# Schematic_proiect_1_v25.net
KiCad netlist of a schematic drawn in EAGLE
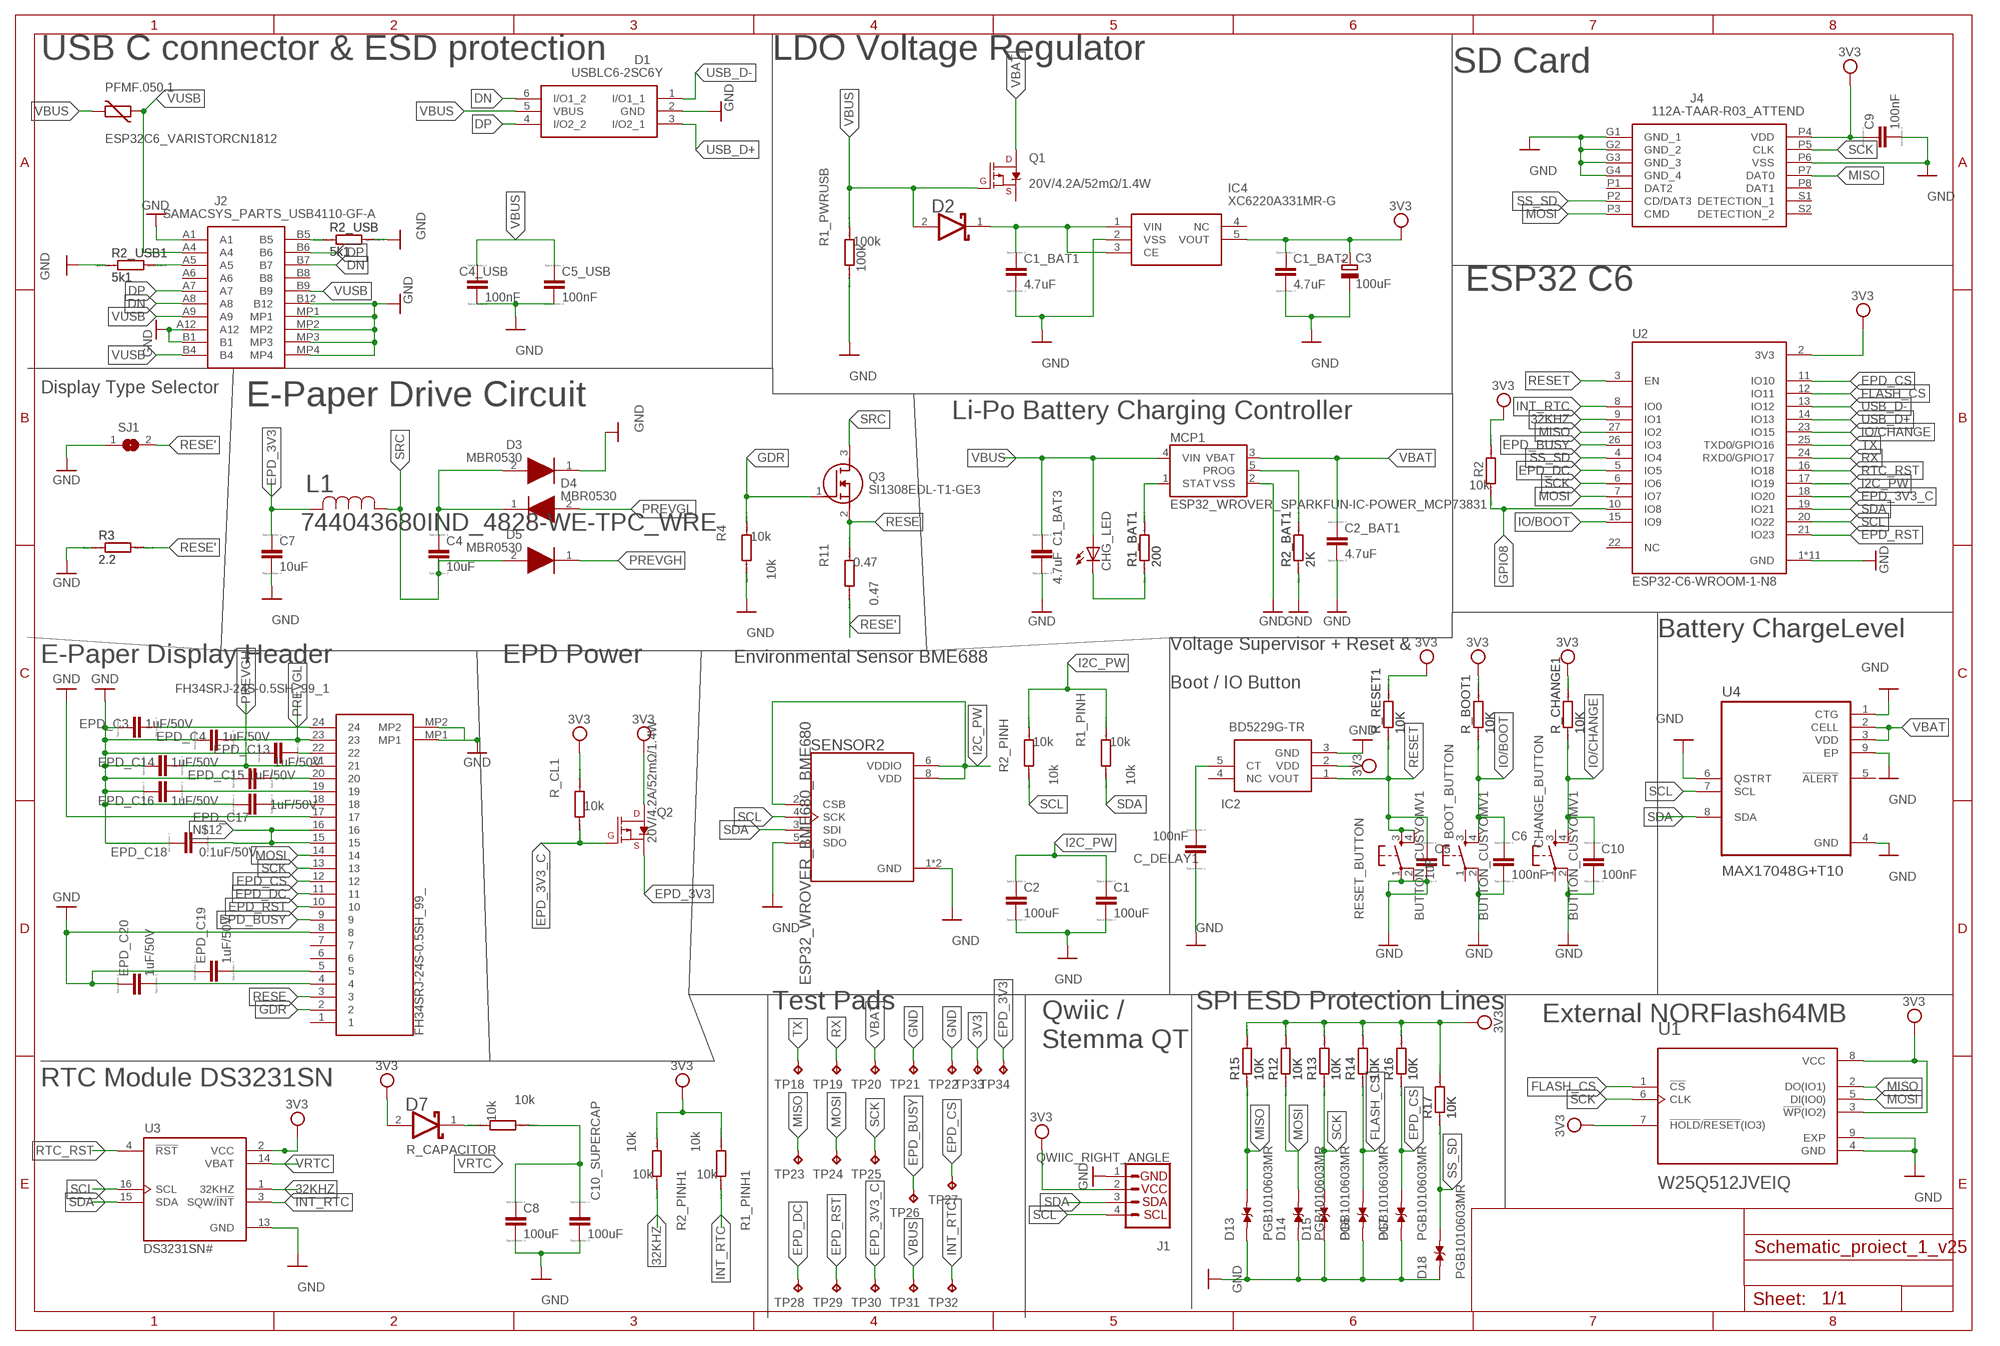
[diagram p0: schematic, sheet 1]

(export (version "E")
  (design (tool "Eeschema 10.0.6"))
  (components
    (comp (ref "BOOT_BUTTON")
      (value "BUTTON_CUSYOMV1")
      (footprint "eagle-import:MYBUTTON")
      (libsource (lib "eagle-import") (part "BUTTON_CUSYOMV1"))
    )
    (comp (ref "C1")
      (value "100uF")
      (footprint "eagle-import:EAGLE-LTSPICE_C0402")
      (libsource (lib "eagle-import") (part "EAGLE-LTSPICE_CC0402"))
    )
    (comp (ref "C1_BAT1")
      (value "4.7uF")
      (footprint "eagle-import:EAGLE-LTSPICE_C0402")
      (libsource (lib "eagle-import") (part "EAGLE-LTSPICE_CC0402"))
    )
    (comp (ref "C1_BAT2")
      (value "4.7uF")
      (footprint "eagle-import:EAGLE-LTSPICE_C0402")
      (libsource (lib "eagle-import") (part "EAGLE-LTSPICE_CC0402"))
    )
    (comp (ref "C1_BAT3")
      (value "4.7uF")
      (footprint "eagle-import:EAGLE-LTSPICE_C0402")
      (libsource (lib "eagle-import") (part "EAGLE-LTSPICE_CC0402"))
    )
    (comp (ref "C2")
      (value "100uF")
      (footprint "eagle-import:EAGLE-LTSPICE_C0402")
      (libsource (lib "eagle-import") (part "EAGLE-LTSPICE_CC0402"))
    )
    (comp (ref "C2_BAT1")
      (value "4.7uF")
      (footprint "eagle-import:EAGLE-LTSPICE_C0402")
      (libsource (lib "eagle-import") (part "EAGLE-LTSPICE_CC0402"))
    )
    (comp (ref "C3")
      (value "100uF")
      (footprint "eagle-import:RCL_CT3528")
      (libsource (lib "eagle-import") (part "RCL_CPOL-EUCT3528"))
    )
    (comp (ref "C4")
      (value "10uF")
      (footprint "eagle-import:EAGLE-LTSPICE_C0402")
      (libsource (lib "eagle-import") (part "EAGLE-LTSPICE_CC0402"))
    )
    (comp (ref "C4_USB")
      (value "100nF")
      (footprint "eagle-import:EAGLE-LTSPICE_C0402")
      (libsource (lib "eagle-import") (part "EAGLE-LTSPICE_CC0402"))
    )
    (comp (ref "C5")
      (value "1uF")
      (footprint "eagle-import:EAGLE-LTSPICE_C0402")
      (libsource (lib "eagle-import") (part "EAGLE-LTSPICE_CC0402"))
    )
    (comp (ref "C5_USB")
      (value "100nF")
      (footprint "eagle-import:EAGLE-LTSPICE_C0402")
      (libsource (lib "eagle-import") (part "EAGLE-LTSPICE_CC0402"))
    )
    (comp (ref "C6")
      (value "100nF")
      (footprint "eagle-import:EAGLE-LTSPICE_C0402")
      (libsource (lib "eagle-import") (part "EAGLE-LTSPICE_CC0402"))
    )
    (comp (ref "C7")
      (value "10uF")
      (footprint "eagle-import:EAGLE-LTSPICE_C0402")
      (libsource (lib "eagle-import") (part "EAGLE-LTSPICE_CC0402"))
    )
    (comp (ref "C8")
      (value "100uF")
      (footprint "eagle-import:EAGLE-LTSPICE_C0402")
      (libsource (lib "eagle-import") (part "EAGLE-LTSPICE_CC0402"))
    )
    (comp (ref "C9")
      (value "100nF")
      (footprint "eagle-import:EAGLE-LTSPICE_C0402")
      (libsource (lib "eagle-import") (part "EAGLE-LTSPICE_CC0402"))
    )
    (comp (ref "C10")
      (value "100nF")
      (footprint "eagle-import:EAGLE-LTSPICE_C0402")
      (libsource (lib "eagle-import") (part "EAGLE-LTSPICE_CC0402"))
    )
    (comp (ref "C10_SUPERCAP")
      (value "100uF")
      (footprint "eagle-import:EAGLE-LTSPICE_C0402")
      (libsource (lib "eagle-import") (part "EAGLE-LTSPICE_CC0402"))
    )
    (comp (ref "CHANGE_BUTTON")
      (value "BUTTON_CUSYOMV1")
      (footprint "eagle-import:MYBUTTON")
      (libsource (lib "eagle-import") (part "BUTTON_CUSYOMV1"))
    )
    (comp (ref "CHG_LED")
      (value "ADAFRUIT_LEDCHIP-LED0603")
      (footprint "eagle-import:ADAFRUIT_CHIP-LED0603")
      (libsource (lib "eagle-import") (part "ADAFRUIT_LEDCHIP-LED0603"))
    )
    (comp (ref "C_DELAY1")
      (value "100nF")
      (footprint "eagle-import:EAGLE-LTSPICE_C0402")
      (libsource (lib "eagle-import") (part "EAGLE-LTSPICE_CC0402"))
    )
    (comp (ref "D1")
      (value "USBLC6-2SC6Y")
      (footprint "eagle-import:SOT95P280X145-6N")
      (fields (field (name "MF") "STMicroelectronics"))
      (libsource (lib "eagle-import") (part "USBLC6-2SC6Y"))
    )
    (comp (ref "D2")
      (value "ESP32_WROVER_AVX---SD0805S020S1R0_AVX_SD0805S020S1R0_0_0AVX_SD0805S020S1R0_0_0")
      (footprint "eagle-import:ESP32_WROVER_AVX---SD0805S020S1R0_AVX_SD0805S020S1R0_0")
      (fields
        (field (name "DIGIKEY_PART_NUMBER") "478-7800-1-ND")
        (field (name "MF") "AVX")
        (field (name "MOUSER_PART_NUMBER") "581-SD0805S020S1R0")
      )
      (libsource (lib "eagle-import") (part "ESP32_WROVER_AVX---SD0805S020S1R0_AVX_SD0805S020S1R0_0_0AVX_SD0805S020S1R0_0_0"))
    )
    (comp (ref "D3")
      (value "MBR0530")
      (footprint "eagle-import:SOD3716X135N")
      (fields (field (name "MF") "ON Semiconductor"))
      (libsource (lib "eagle-import") (part "MBR0530"))
    )
    (comp (ref "D4")
      (value "MBR0530")
      (footprint "eagle-import:SOD3716X135N")
      (fields (field (name "MF") "ON Semiconductor"))
      (libsource (lib "eagle-import") (part "MBR0530"))
    )
    (comp (ref "D5")
      (value "MBR0530")
      (footprint "eagle-import:SOD3716X135N")
      (fields (field (name "MF") "ON Semiconductor"))
      (libsource (lib "eagle-import") (part "MBR0530"))
    )
    (comp (ref "D7")
      (value "ESP32_WROVER_AVX---SD0805S020S1R0_AVX_SD0805S020S1R0_0_0AVX_SD0805S020S1R0_0_0")
      (footprint "eagle-import:ESP32_WROVER_AVX---SD0805S020S1R0_AVX_SD0805S020S1R0_0")
      (fields
        (field (name "DIGIKEY_PART_NUMBER") "478-7800-1-ND")
        (field (name "MF") "AVX")
        (field (name "MOUSER_PART_NUMBER") "581-SD0805S020S1R0")
      )
      (libsource (lib "eagle-import") (part "ESP32_WROVER_AVX---SD0805S020S1R0_AVX_SD0805S020S1R0_0_0AVX_SD0805S020S1R0_0_0"))
    )
    (comp (ref "D13")
      (value "PGB1010603MR")
      (footprint "eagle-import:DIOC1608X36N")
      (fields (field (name "MF") "Littelfuse Inc."))
      (libsource (lib "eagle-import") (part "PGB1010603MR"))
    )
    (comp (ref "D14")
      (value "PGB1010603MR")
      (footprint "eagle-import:DIOC1608X36N")
      (fields (field (name "MF") "Littelfuse Inc."))
      (libsource (lib "eagle-import") (part "PGB1010603MR"))
    )
    (comp (ref "D15")
      (value "PGB1010603MR")
      (footprint "eagle-import:DIOC1608X36N")
      (fields (field (name "MF") "Littelfuse Inc."))
      (libsource (lib "eagle-import") (part "PGB1010603MR"))
    )
    (comp (ref "D16")
      (value "PGB1010603MR")
      (footprint "eagle-import:DIOC1608X36N")
      (fields (field (name "MF") "Littelfuse Inc."))
      (libsource (lib "eagle-import") (part "PGB1010603MR"))
    )
    (comp (ref "D17")
      (value "PGB1010603MR")
      (footprint "eagle-import:DIOC1608X36N")
      (fields (field (name "MF") "Littelfuse Inc."))
      (libsource (lib "eagle-import") (part "PGB1010603MR"))
    )
    (comp (ref "D18")
      (value "PGB1010603MR")
      (footprint "eagle-import:DIOC1608X36N")
      (fields (field (name "MF") "Littelfuse Inc."))
      (libsource (lib "eagle-import") (part "PGB1010603MR"))
    )
    (comp (ref "EPD_C3")
      (value "1uF/50V")
      (footprint "eagle-import:EAGLE-LTSPICE_C0402")
      (libsource (lib "eagle-import") (part "EAGLE-LTSPICE_CC0402"))
    )
    (comp (ref "EPD_C4")
      (value "1uF/50V")
      (footprint "eagle-import:EAGLE-LTSPICE_C0402")
      (libsource (lib "eagle-import") (part "EAGLE-LTSPICE_CC0402"))
    )
    (comp (ref "EPD_C13")
      (value "1uF/50V")
      (footprint "eagle-import:EAGLE-LTSPICE_C0402")
      (libsource (lib "eagle-import") (part "EAGLE-LTSPICE_CC0402"))
    )
    (comp (ref "EPD_C14")
      (value "1uF/50V")
      (footprint "eagle-import:EAGLE-LTSPICE_C0402")
      (libsource (lib "eagle-import") (part "EAGLE-LTSPICE_CC0402"))
    )
    (comp (ref "EPD_C15")
      (value "1uF/50V")
      (footprint "eagle-import:EAGLE-LTSPICE_C0402")
      (libsource (lib "eagle-import") (part "EAGLE-LTSPICE_CC0402"))
    )
    (comp (ref "EPD_C16")
      (value "1uF/50V")
      (footprint "eagle-import:EAGLE-LTSPICE_C0402")
      (libsource (lib "eagle-import") (part "EAGLE-LTSPICE_CC0402"))
    )
    (comp (ref "EPD_C17")
      (value "1uF/50V")
      (footprint "eagle-import:EAGLE-LTSPICE_C0402")
      (libsource (lib "eagle-import") (part "EAGLE-LTSPICE_CC0402"))
    )
    (comp (ref "EPD_C18")
      (value "0.1uF/50V")
      (footprint "eagle-import:EAGLE-LTSPICE_C0402")
      (libsource (lib "eagle-import") (part "EAGLE-LTSPICE_CC0402"))
    )
    (comp (ref "EPD_C19")
      (value "1uF/50V")
      (footprint "eagle-import:EAGLE-LTSPICE_C0402")
      (libsource (lib "eagle-import") (part "EAGLE-LTSPICE_CC0402"))
    )
    (comp (ref "EPD_C20")
      (value "1uF/50V")
      (footprint "eagle-import:EAGLE-LTSPICE_C0402")
      (libsource (lib "eagle-import") (part "EAGLE-LTSPICE_CC0402"))
    )
    (comp (ref "FH34SRJ-24S-0.5SH_99_1")
      (value "FH34SRJ-24S-0.5SH_99_")
      (footprint "eagle-import:FH34SRJ24S05SH99")
      (fields
        (field (name "MANUFACTURER_PART_NUMBER") "FH34SRJ-24S-0.5SH(99)")
        (field (name "MOUSER_PART_NUMBER") "798-FH34SRJ24S05SH99")
      )
      (libsource (lib "eagle-import") (part "FH34SRJ-24S-0.5SH_99_"))
    )
    (comp (ref "IC2")
      (value "BD5229G-TR")
      (footprint "eagle-import:SOT95P280X125-5N")
      (fields (field (name "MOUSER_PART_NUMBER") "755-BD5229G-TR"))
      (libsource (lib "eagle-import") (part "BD5229G-TR"))
    )
    (comp (ref "IC4")
      (value "XC6220A331MR-G")
      (footprint "eagle-import:SOT95P280X120-5N")
      (fields (field (name "MOUSER_PART_NUMBER") "865-XC6220A331MR-G"))
      (libsource (lib "eagle-import") (part "XC6220A331MR-G"))
    )
    (comp (ref "J1")
      (value "QWIIC_RIGHT_ANGLE")
      (footprint "eagle-import:JST04_1MM_RA")
      (libsource (lib "eagle-import") (part "QWIIC_CONNECTORJS-1MM"))
    )
    (comp (ref "J2")
      (value "SAMACSYS_PARTS_USB4110-GF-A")
      (footprint "eagle-import:SAMACSYS_PARTS_USB4110GFA")
      (fields
        (field (name "MANUFACTURER_PART_NUMBER") "USB4110-GF-A")
        (field (name "MOUSER_PART_NUMBER") "640-USB4110-GF-A")
      )
      (libsource (lib "eagle-import") (part "SAMACSYS_PARTS_USB4110-GF-A"))
    )
    (comp (ref "J4")
      (value "112A-TAAR-R03_ATTEND")
      (footprint "eagle-import:112ATAARR03ATTEND")
      (fields (field (name "MANUFACTURER_PART_NUMBER") "112A-TAAR-R03 ATTEND"))
      (libsource (lib "eagle-import") (part "112A-TAAR-R03_ATTEND"))
    )
    (comp (ref "L1")
      (value "744043680IND_4828-WE-TPC_WRE")
      (footprint "eagle-import:IND_4828-WE-TPC_WRE")
      (fields
        (field (name "MANUFACTURER_PART_NUMBER") "744043680")
        (field (name "COPYRIGHT") "Copyright (C) 2024 Ultra Librarian. All rights reserved.")
      )
      (libsource (lib "eagle-import") (part "744043680IND_4828-WE-TPC_WRE"))
    )
    (comp (ref "MCP1")
      (value "ESP32_WROVER_SPARKFUN-IC-POWER_MCP73831")
      (footprint "eagle-import:ESP32_WROVER_SPARKFUN-IC-POWER_SOT23-5")
      (libsource (lib "eagle-import") (part "ESP32_WROVER_SPARKFUN-IC-POWER_MCP73831"))
    )
    (comp (ref "PFMF.050.1")
      (value "ESP32C6_VARISTORCN1812")
      (footprint "eagle-import:ESP32C6_VARISTOR_CT_CN1812")
      (libsource (lib "eagle-import") (part "ESP32C6_VARISTORCN1812"))
    )
    (comp (ref "Q1")
      (value "20V/4.2A/52mΩ/1.4W")
      (footprint "eagle-import:ESP32_WROVER_SPARKFUN-DISCRETESEMI_SOT23-3")
      (libsource (lib "eagle-import") (part "ESP32_WROVER_SPARKFUN-DISCRETESEMI_MOSFET_PCH-DMG2305UX-7"))
    )
    (comp (ref "Q2")
      (value "20V/4.2A/52mΩ/1.4W")
      (footprint "eagle-import:ESP32_WROVER_SPARKFUN-DISCRETESEMI_SOT23-3")
      (libsource (lib "eagle-import") (part "ESP32_WROVER_SPARKFUN-DISCRETESEMI_MOSFET_PCH-DMG2305UX-7"))
    )
    (comp (ref "Q3")
      (value "SI1308EDL-T1-GE3")
      (footprint "eagle-import:SOT65P210X110-3N")
      (fields (field (name "MF") "Vishay Siliconix"))
      (libsource (lib "eagle-import") (part "SI1308EDL-T1-GE3"))
    )
    (comp (ref "R1_BAT1")
      (value "200")
      (footprint "eagle-import:ESP32_WROVER_EAGLE-LTSPICE_R0402")
      (libsource (lib "eagle-import") (part "ESP32_WROVER_EAGLE-LTSPICE_RR0402"))
    )
    (comp (ref "R1_PINH")
      (value "10k")
      (footprint "eagle-import:ESP32_WROVER_EAGLE-LTSPICE_R0402")
      (libsource (lib "eagle-import") (part "ESP32_WROVER_EAGLE-LTSPICE_RR0402"))
    )
    (comp (ref "R1_PINH1")
      (value "10k")
      (footprint "eagle-import:ESP32_WROVER_EAGLE-LTSPICE_R0402")
      (libsource (lib "eagle-import") (part "ESP32_WROVER_EAGLE-LTSPICE_RR0402"))
    )
    (comp (ref "R1_PWRUSB")
      (value "100k")
      (footprint "eagle-import:ESP32_WROVER_EAGLE-LTSPICE_R0402")
      (libsource (lib "eagle-import") (part "ESP32_WROVER_EAGLE-LTSPICE_RR0402"))
    )
    (comp (ref "R2")
      (value "10k")
      (footprint "eagle-import:ESP32_WROVER_EAGLE-LTSPICE_R0402")
      (libsource (lib "eagle-import") (part "ESP32_WROVER_EAGLE-LTSPICE_RR0402"))
    )
    (comp (ref "R2_BAT1")
      (value "2K")
      (footprint "eagle-import:ESP32_WROVER_EAGLE-LTSPICE_R0402")
      (libsource (lib "eagle-import") (part "ESP32_WROVER_EAGLE-LTSPICE_RR0402"))
    )
    (comp (ref "R2_PINH")
      (value "10k")
      (footprint "eagle-import:ESP32_WROVER_EAGLE-LTSPICE_R0402")
      (libsource (lib "eagle-import") (part "ESP32_WROVER_EAGLE-LTSPICE_RR0402"))
    )
    (comp (ref "R2_PINH1")
      (value "10k")
      (footprint "eagle-import:ESP32_WROVER_EAGLE-LTSPICE_R0402")
      (libsource (lib "eagle-import") (part "ESP32_WROVER_EAGLE-LTSPICE_RR0402"))
    )
    (comp (ref "R2_USB")
      (value "5k1")
      (footprint "eagle-import:ESP32_WROVER_EAGLE-LTSPICE_R0402")
      (libsource (lib "eagle-import") (part "ESP32_WROVER_EAGLE-LTSPICE_RR0402"))
    )
    (comp (ref "R2_USB1")
      (value "5k1")
      (footprint "eagle-import:ESP32_WROVER_EAGLE-LTSPICE_R0402")
      (libsource (lib "eagle-import") (part "ESP32_WROVER_EAGLE-LTSPICE_RR0402"))
    )
    (comp (ref "R3")
      (value "2.2")
      (footprint "eagle-import:ESP32_WROVER_EAGLE-LTSPICE_R0402")
      (libsource (lib "eagle-import") (part "ESP32_WROVER_EAGLE-LTSPICE_RR0402"))
    )
    (comp (ref "R4")
      (value "10k")
      (footprint "eagle-import:ESP32_WROVER_EAGLE-LTSPICE_R0402")
      (libsource (lib "eagle-import") (part "ESP32_WROVER_EAGLE-LTSPICE_RR0402"))
    )
    (comp (ref "R11")
      (value "0.47")
      (footprint "eagle-import:ESP32_WROVER_EAGLE-LTSPICE_R0402")
      (libsource (lib "eagle-import") (part "ESP32_WROVER_EAGLE-LTSPICE_RR0402"))
    )
    (comp (ref "R12")
      (value "10K")
      (footprint "eagle-import:ESP32_WROVER_EAGLE-LTSPICE_R0402")
      (libsource (lib "eagle-import") (part "ESP32_WROVER_EAGLE-LTSPICE_RR0402"))
    )
    (comp (ref "R13")
      (value "10K")
      (footprint "eagle-import:ESP32_WROVER_EAGLE-LTSPICE_R0402")
      (libsource (lib "eagle-import") (part "ESP32_WROVER_EAGLE-LTSPICE_RR0402"))
    )
    (comp (ref "R14")
      (value "10K")
      (footprint "eagle-import:ESP32_WROVER_EAGLE-LTSPICE_R0402")
      (libsource (lib "eagle-import") (part "ESP32_WROVER_EAGLE-LTSPICE_RR0402"))
    )
    (comp (ref "R15")
      (value "10K")
      (footprint "eagle-import:ESP32_WROVER_EAGLE-LTSPICE_R0402")
      (libsource (lib "eagle-import") (part "ESP32_WROVER_EAGLE-LTSPICE_RR0402"))
    )
    (comp (ref "R16")
      (value "10K")
      (footprint "eagle-import:ESP32_WROVER_EAGLE-LTSPICE_R0402")
      (libsource (lib "eagle-import") (part "ESP32_WROVER_EAGLE-LTSPICE_RR0402"))
    )
    (comp (ref "R17")
      (value "10K")
      (footprint "eagle-import:ESP32_WROVER_EAGLE-LTSPICE_R0402")
      (libsource (lib "eagle-import") (part "ESP32_WROVER_EAGLE-LTSPICE_RR0402"))
    )
    (comp (ref "RESET_BUTTON")
      (value "BUTTON_CUSYOMV1")
      (footprint "eagle-import:MYBUTTON")
      (libsource (lib "eagle-import") (part "BUTTON_CUSYOMV1"))
    )
    (comp (ref "R_BOOT1")
      (value "10K")
      (footprint "eagle-import:ESP32_WROVER_EAGLE-LTSPICE_R0402")
      (libsource (lib "eagle-import") (part "ESP32_WROVER_EAGLE-LTSPICE_RR0402"))
    )
    (comp (ref "R_CAPACITOR")
      (value "10k")
      (footprint "eagle-import:ESP32_WROVER_EAGLE-LTSPICE_R0402")
      (libsource (lib "eagle-import") (part "ESP32_WROVER_EAGLE-LTSPICE_RR0402"))
    )
    (comp (ref "R_CHANGE1")
      (value "10K")
      (footprint "eagle-import:ESP32_WROVER_EAGLE-LTSPICE_R0402")
      (libsource (lib "eagle-import") (part "ESP32_WROVER_EAGLE-LTSPICE_RR0402"))
    )
    (comp (ref "R_CL1")
      (value "10k")
      (footprint "eagle-import:ESP32_WROVER_EAGLE-LTSPICE_R0402")
      (libsource (lib "eagle-import") (part "ESP32_WROVER_EAGLE-LTSPICE_RR0402"))
    )
    (comp (ref "R_RESET1")
      (value "10K")
      (footprint "eagle-import:ESP32_WROVER_EAGLE-LTSPICE_R0402")
      (libsource (lib "eagle-import") (part "ESP32_WROVER_EAGLE-LTSPICE_RR0402"))
    )
    (comp (ref "SENSOR2")
      (value "ESP32_WROVER_BME680_BME680")
      (footprint "eagle-import:ESP32_WROVER_BME680_PSON80P300X300X100-8N")
      (fields (field (name "MF") "Bosch Sensortec") (field (name "MP") "BME680"))
      (libsource (lib "eagle-import") (part "ESP32_WROVER_BME680_BME680"))
    )
    (comp (ref "SJ1") (value "SJ") (footprint "eagle-import:SJ") (libsource (lib "eagle-import") (part "SJ")))
    (comp (ref "TP18")
      (value "TPTP20R")
      (footprint "eagle-import:TP20R")
      (libsource (lib "eagle-import") (part "TPTP20R"))
    )
    (comp (ref "TP19")
      (value "TPTP20R")
      (footprint "eagle-import:TP20R")
      (libsource (lib "eagle-import") (part "TPTP20R"))
    )
    (comp (ref "TP20")
      (value "TPTP20R")
      (footprint "eagle-import:TP20R")
      (libsource (lib "eagle-import") (part "TPTP20R"))
    )
    (comp (ref "TP21")
      (value "TPTP20R")
      (footprint "eagle-import:TP20R")
      (libsource (lib "eagle-import") (part "TPTP20R"))
    )
    (comp (ref "TP22")
      (value "TPTP20R")
      (footprint "eagle-import:TP20R")
      (libsource (lib "eagle-import") (part "TPTP20R"))
    )
    (comp (ref "TP23")
      (value "TPTP20R")
      (footprint "eagle-import:TP20R")
      (libsource (lib "eagle-import") (part "TPTP20R"))
    )
    (comp (ref "TP24")
      (value "TPTP20R")
      (footprint "eagle-import:TP20R")
      (libsource (lib "eagle-import") (part "TPTP20R"))
    )
    (comp (ref "TP25")
      (value "TPTP20R")
      (footprint "eagle-import:TP20R")
      (libsource (lib "eagle-import") (part "TPTP20R"))
    )
    (comp (ref "TP26")
      (value "TPTP20R")
      (footprint "eagle-import:TP20R")
      (libsource (lib "eagle-import") (part "TPTP20R"))
    )
    (comp (ref "TP27")
      (value "TPTP20R")
      (footprint "eagle-import:TP20R")
      (libsource (lib "eagle-import") (part "TPTP20R"))
    )
    (comp (ref "TP28")
      (value "TPTP20R")
      (footprint "eagle-import:TP20R")
      (libsource (lib "eagle-import") (part "TPTP20R"))
    )
    (comp (ref "TP29")
      (value "TPTP20R")
      (footprint "eagle-import:TP20R")
      (libsource (lib "eagle-import") (part "TPTP20R"))
    )
    (comp (ref "TP30")
      (value "TPTP20R")
      (footprint "eagle-import:TP20R")
      (libsource (lib "eagle-import") (part "TPTP20R"))
    )
    (comp (ref "TP31")
      (value "TPTP20R")
      (footprint "eagle-import:TP20R")
      (libsource (lib "eagle-import") (part "TPTP20R"))
    )
    (comp (ref "TP32")
      (value "TPTP20R")
      (footprint "eagle-import:TP20R")
      (libsource (lib "eagle-import") (part "TPTP20R"))
    )
    (comp (ref "TP33")
      (value "TPTP20R")
      (footprint "eagle-import:TP20R")
      (libsource (lib "eagle-import") (part "TPTP20R"))
    )
    (comp (ref "TP34")
      (value "TPTP20R")
      (footprint "eagle-import:TP20R")
      (libsource (lib "eagle-import") (part "TPTP20R"))
    )
    (comp (ref "U1")
      (value "W25Q512JVEIQ")
      (footprint "eagle-import:SON127P600X800X80-9N")
      (fields (field (name "MF") "Winbond Electronics"))
      (libsource (lib "eagle-import") (part "W25Q512JVEIQ"))
    )
    (comp (ref "U2")
      (value "ESP32-C6-WROOM-1-N8")
      (footprint "eagle-import:XCVR_ESP32-C6-WROOM-1-N8")
      (fields (field (name "MF") "Espressif Systems"))
      (libsource (lib "eagle-import") (part "ESP32-C6-WROOM-1-N8"))
    )
    (comp (ref "U3")
      (value "DS3231SN#")
      (footprint "eagle-import:SOIC127P1032X265-16N")
      (fields (field (name "MF") "Analog Devices"))
      (libsource (lib "eagle-import") (part "DS3231SN#"))
    )
    (comp (ref "U4")
      (value "MAX17048G+T10")
      (footprint "eagle-import:SON50P200X200X80-9N")
      (fields (field (name "MF") "Analog Devices"))
      (libsource (lib "eagle-import") (part "MAX17048G+T10"))
    )
  )
  (nets
    (net (code "1") (name "3V3") (class "Default")
      (node (ref "C1_BAT2") (pin "1") (pinfunction "1_1") (pintype "passive"))
      (node (ref "C3") (pin "+") (pinfunction "+_+") (pintype "passive"))
      (node (ref "C9") (pin "1") (pinfunction "1_1") (pintype "passive"))
      (node (ref "D7") (pin "2") (pinfunction "ANODE_2") (pintype "bidirectional"))
      (node (ref "IC2") (pin "2") (pinfunction "VDD_2") (pintype "bidirectional"))
      (node (ref "IC4") (pin "5") (pinfunction "VOUT_5") (pintype "bidirectional"))
      (node (ref "J1") (pin "2") (pinfunction "2_2") (pintype "power_in"))
      (node (ref "J4") (pin "P4") (pinfunction "VDD_P4") (pintype "bidirectional"))
      (node (ref "Q2") (pin "3") (pinfunction "D_3") (pintype "bidirectional"))
      (node (ref "R12") (pin "2") (pinfunction "2_2") (pintype "passive"))
      (node (ref "R13") (pin "2") (pinfunction "2_2") (pintype "passive"))
      (node (ref "R14") (pin "2") (pinfunction "2_2") (pintype "passive"))
      (node (ref "R15") (pin "2") (pinfunction "2_2") (pintype "passive"))
      (node (ref "R16") (pin "2") (pinfunction "2_2") (pintype "passive"))
      (node (ref "R17") (pin "2") (pinfunction "2_2") (pintype "passive"))
      (node (ref "R1_PINH1") (pin "1") (pinfunction "1_1") (pintype "passive"))
      (node (ref "R2") (pin "2") (pinfunction "2_2") (pintype "passive"))
      (node (ref "R2_PINH1") (pin "1") (pinfunction "1_1") (pintype "passive"))
      (node (ref "R_BOOT1") (pin "2") (pinfunction "2_2") (pintype "passive"))
      (node (ref "R_CHANGE1") (pin "2") (pinfunction "2_2") (pintype "passive"))
      (node (ref "R_CL1") (pin "2") (pinfunction "2_2") (pintype "passive"))
      (node (ref "R_RESET1") (pin "2") (pinfunction "2_2") (pintype "passive"))
      (node (ref "TP33") (pin "TP") (pinfunction "TP_TP") (pintype "input"))
      (node (ref "U1") (pin "3") (pinfunction "~{WP}(IO2)_3") (pintype "bidirectional"))
      (node (ref "U1") (pin "7") (pinfunction "~{HOLD}/~{RESET}(IO3)_7") (pintype "bidirectional"))
      (node (ref "U1") (pin "8") (pinfunction "VCC_8") (pintype "power_in"))
      (node (ref "U2") (pin "2") (pinfunction "3V3_2") (pintype "power_in"))
      (node (ref "U3") (pin "2") (pinfunction "VCC_2") (pintype "power_in"))
    )
    (net (code "2") (name "32KHZ") (class "Default")
      (node (ref "R2_PINH1") (pin "2") (pinfunction "2_2") (pintype "passive"))
      (node (ref "U2") (pin "9") (pinfunction "IO1_9") (pintype "bidirectional"))
      (node (ref "U3") (pin "1") (pinfunction "32KHZ_1") (pintype "output"))
    )
    (net (code "3") (name "DN") (class "Default")
      (node (ref "D1") (pin "6") (pinfunction "I/O1_2_6") (pintype "bidirectional"))
      (node (ref "J2") (pin "A8") (pinfunction "A8_A8") (pintype "bidirectional"))
      (node (ref "J2") (pin "B7") (pinfunction "B7_B7") (pintype "bidirectional"))
    )
    (net (code "4") (name "DP") (class "Default")
      (node (ref "D1") (pin "4") (pinfunction "I/O2_2_4") (pintype "bidirectional"))
      (node (ref "J2") (pin "A7") (pinfunction "A7_A7") (pintype "bidirectional"))
      (node (ref "J2") (pin "B6") (pinfunction "B6_B6") (pintype "bidirectional"))
    )
    (net (code "5") (name "EPD_3V3") (class "Default")
      (node (ref "C7") (pin "1") (pinfunction "1_1") (pintype "passive"))
      (node (ref "L1") (pin "2") (pinfunction "2_2") (pintype "passive"))
      (node (ref "Q2") (pin "2") (pinfunction "S_2") (pintype "bidirectional"))
      (node (ref "TP34") (pin "TP") (pinfunction "TP_TP") (pintype "input"))
    )
    (net (code "6") (name "EPD_3V3_C") (class "Default")
      (node (ref "Q2") (pin "1") (pinfunction "G_1") (pintype "bidirectional"))
      (node (ref "R_CL1") (pin "1") (pinfunction "1_1") (pintype "passive"))
      (node (ref "TP30") (pin "TP") (pinfunction "TP_TP") (pintype "input"))
      (node (ref "U2") (pin "18") (pinfunction "IO20_18") (pintype "bidirectional"))
    )
    (net (code "7") (name "EPD_BUSY") (class "Default")
      (node (ref "FH34SRJ-24S-0.5SH_99_1") (pin "9") (pinfunction "9_9") (pintype "bidirectional"))
      (node (ref "TP26") (pin "TP") (pinfunction "TP_TP") (pintype "input"))
      (node (ref "U2") (pin "26") (pinfunction "IO3_26") (pintype "bidirectional"))
    )
    (net (code "8") (name "EPD_CS") (class "Default")
      (node (ref "D17") (pin "2") (pinfunction "2_2") (pintype "passive"))
      (node (ref "FH34SRJ-24S-0.5SH_99_1") (pin "12") (pinfunction "12_12") (pintype "bidirectional"))
      (node (ref "R16") (pin "1") (pinfunction "1_1") (pintype "passive"))
      (node (ref "TP27") (pin "TP") (pinfunction "TP_TP") (pintype "input"))
      (node (ref "U2") (pin "11") (pinfunction "IO10_11") (pintype "bidirectional"))
    )
    (net (code "9") (name "EPD_DC") (class "Default")
      (node (ref "FH34SRJ-24S-0.5SH_99_1") (pin "11") (pinfunction "11_11") (pintype "bidirectional"))
      (node (ref "TP28") (pin "TP") (pinfunction "TP_TP") (pintype "input"))
      (node (ref "U2") (pin "5") (pinfunction "IO5_5") (pintype "bidirectional"))
    )
    (net (code "10") (name "EPD_RST") (class "Default")
      (node (ref "FH34SRJ-24S-0.5SH_99_1") (pin "10") (pinfunction "10_10") (pintype "bidirectional"))
      (node (ref "TP29") (pin "TP") (pinfunction "TP_TP") (pintype "input"))
      (node (ref "U2") (pin "21") (pinfunction "IO23_21") (pintype "bidirectional"))
    )
    (net (code "11") (name "FLASH_CS") (class "Default")
      (node (ref "D16") (pin "2") (pinfunction "2_2") (pintype "passive"))
      (node (ref "R14") (pin "1") (pinfunction "1_1") (pintype "passive"))
      (node (ref "U1") (pin "1") (pinfunction "~{CS}_1") (pintype "input"))
      (node (ref "U2") (pin "12") (pinfunction "IO11_12") (pintype "bidirectional"))
    )
    (net (code "12") (name "GDR") (class "Default")
      (node (ref "FH34SRJ-24S-0.5SH_99_1") (pin "2") (pinfunction "2_2") (pintype "bidirectional"))
      (node (ref "Q3") (pin "1") (pinfunction "G_1") (pintype "bidirectional"))
      (node (ref "R4") (pin "2") (pinfunction "2_2") (pintype "passive"))
    )
    (net (code "13") (name "GND") (class "Default")
      (node (ref "BOOT_BUTTON") (pin "2") (pinfunction "2_2") (pintype "passive"))
      (node (ref "C1") (pin "2") (pinfunction "2_2") (pintype "passive"))
      (node (ref "C10") (pin "2") (pinfunction "2_2") (pintype "passive"))
      (node (ref "C10_SUPERCAP") (pin "2") (pinfunction "2_2") (pintype "passive"))
      (node (ref "C1_BAT1") (pin "2") (pinfunction "2_2") (pintype "passive"))
      (node (ref "C1_BAT2") (pin "2") (pinfunction "2_2") (pintype "passive"))
      (node (ref "C1_BAT3") (pin "2") (pinfunction "2_2") (pintype "passive"))
      (node (ref "C2") (pin "2") (pinfunction "2_2") (pintype "passive"))
      (node (ref "C2_BAT1") (pin "2") (pinfunction "2_2") (pintype "passive"))
      (node (ref "C3") (pin "-") (pinfunction "-_-") (pintype "passive"))
      (node (ref "C4_USB") (pin "2") (pinfunction "2_2") (pintype "passive"))
      (node (ref "C5") (pin "2") (pinfunction "2_2") (pintype "passive"))
      (node (ref "C5_USB") (pin "2") (pinfunction "2_2") (pintype "passive"))
      (node (ref "C6") (pin "2") (pinfunction "2_2") (pintype "passive"))
      (node (ref "C7") (pin "2") (pinfunction "2_2") (pintype "passive"))
      (node (ref "C8") (pin "2") (pinfunction "2_2") (pintype "passive"))
      (node (ref "C9") (pin "2") (pinfunction "2_2") (pintype "passive"))
      (node (ref "CHANGE_BUTTON") (pin "2") (pinfunction "2_2") (pintype "passive"))
      (node (ref "C_DELAY1") (pin "1") (pinfunction "1_1") (pintype "passive"))
      (node (ref "D1") (pin "2") (pinfunction "GND_2") (pintype "bidirectional"))
      (node (ref "D13") (pin "1") (pinfunction "1_1") (pintype "passive"))
      (node (ref "D14") (pin "1") (pinfunction "1_1") (pintype "passive"))
      (node (ref "D15") (pin "1") (pinfunction "1_1") (pintype "passive"))
      (node (ref "D16") (pin "1") (pinfunction "1_1") (pintype "passive"))
      (node (ref "D17") (pin "1") (pinfunction "1_1") (pintype "passive"))
      (node (ref "D18") (pin "1") (pinfunction "1_1") (pintype "passive"))
      (node (ref "D3") (pin "1") (pinfunction "K_1") (pintype "bidirectional"))
      (node (ref "EPD_C13") (pin "1") (pinfunction "1_1") (pintype "passive"))
      (node (ref "EPD_C14") (pin "1") (pinfunction "1_1") (pintype "passive"))
      (node (ref "EPD_C15") (pin "1") (pinfunction "1_1") (pintype "passive"))
      (node (ref "EPD_C16") (pin "1") (pinfunction "1_1") (pintype "passive"))
      (node (ref "EPD_C17") (pin "1") (pinfunction "1_1") (pintype "passive"))
      (node (ref "EPD_C18") (pin "1") (pinfunction "1_1") (pintype "passive"))
      (node (ref "EPD_C19") (pin "1") (pinfunction "1_1") (pintype "passive"))
      (node (ref "EPD_C20") (pin "1") (pinfunction "1_1") (pintype "passive"))
      (node (ref "EPD_C3") (pin "1") (pinfunction "1_1") (pintype "passive"))
      (node (ref "EPD_C4") (pin "1") (pinfunction "1_1") (pintype "passive"))
      (node (ref "FH34SRJ-24S-0.5SH_99_1") (pin "17") (pinfunction "17_17") (pintype "bidirectional"))
      (node (ref "FH34SRJ-24S-0.5SH_99_1") (pin "8") (pinfunction "8_8") (pintype "bidirectional"))
      (node (ref "FH34SRJ-24S-0.5SH_99_1") (pin "MP1") (pinfunction "MP1_MP1") (pintype "bidirectional"))
      (node (ref "FH34SRJ-24S-0.5SH_99_1") (pin "MP2") (pinfunction "MP2_MP2") (pintype "bidirectional"))
      (node (ref "IC2") (pin "3") (pinfunction "GND_3") (pintype "bidirectional"))
      (node (ref "IC4") (pin "2") (pinfunction "VSS_2") (pintype "bidirectional"))
      (node (ref "J1") (pin "1") (pinfunction "1_1") (pintype "power_in"))
      (node (ref "J2") (pin "A1") (pinfunction "A1_A1") (pintype "bidirectional"))
      (node (ref "J2") (pin "A12") (pinfunction "A12_A12") (pintype "bidirectional"))
      (node (ref "J2") (pin "B1") (pinfunction "B1_B1") (pintype "bidirectional"))
      (node (ref "J2") (pin "B12") (pinfunction "B12_B12") (pintype "bidirectional"))
      (node (ref "J2") (pin "MP1") (pinfunction "MP1_MP1") (pintype "bidirectional"))
      (node (ref "J2") (pin "MP2") (pinfunction "MP2_MP2") (pintype "bidirectional"))
      (node (ref "J2") (pin "MP3") (pinfunction "MP3_MP3") (pintype "bidirectional"))
      (node (ref "J2") (pin "MP4") (pinfunction "MP4_MP4") (pintype "bidirectional"))
      (node (ref "J4") (pin "G1") (pinfunction "GND_1_G1") (pintype "bidirectional"))
      (node (ref "J4") (pin "G2") (pinfunction "GND_2_G2") (pintype "bidirectional"))
      (node (ref "J4") (pin "G3") (pinfunction "GND_3_G3") (pintype "bidirectional"))
      (node (ref "J4") (pin "G4") (pinfunction "GND_4_G4") (pintype "bidirectional"))
      (node (ref "J4") (pin "P6") (pinfunction "VSS_P6") (pintype "bidirectional"))
      (node (ref "MCP1") (pin "2") (pinfunction "VSS_2") (pintype "power_in"))
      (node (ref "R1_PWRUSB") (pin "1") (pinfunction "1_1") (pintype "passive"))
      (node (ref "R2_BAT1") (pin "1") (pinfunction "1_1") (pintype "passive"))
      (node (ref "R2_USB") (pin "2") (pinfunction "2_2") (pintype "passive"))
      (node (ref "R2_USB1") (pin "1") (pinfunction "1_1") (pintype "passive"))
      (node (ref "R3") (pin "1") (pinfunction "1_1") (pintype "passive"))
      (node (ref "R4") (pin "1") (pinfunction "1_1") (pintype "passive"))
      (node (ref "RESET_BUTTON") (pin "1") (pinfunction "1_1") (pintype "passive"))
      (node (ref "RESET_BUTTON") (pin "2") (pinfunction "2_2") (pintype "passive"))
      (node (ref "SENSOR2") (pin "1") (pinfunction "GND_1") (pintype "power_in"))
      (node (ref "SENSOR2") (pin "5") (pinfunction "SDO_5") (pintype "bidirectional"))
      (node (ref "SENSOR2") (pin "7") (pinfunction "GND_7") (pintype "power_in"))
      (node (ref "SJ1") (pin "1") (pinfunction "1_1") (pintype "passive"))
      (node (ref "TP21") (pin "TP") (pinfunction "TP_TP") (pintype "input"))
      (node (ref "TP22") (pin "TP") (pinfunction "TP_TP") (pintype "input"))
      (node (ref "U1") (pin "4") (pinfunction "GND_4") (pintype "power_in"))
      (node (ref "U1") (pin "9") (pinfunction "EXP_9") (pintype "passive"))
      (node (ref "U2") (pin "1") (pinfunction "GND_1") (pintype "power_in"))
      (node (ref "U2") (pin "28") (pinfunction "GND_28") (pintype "power_in"))
      (node (ref "U2") (pin "29_1") (pinfunction "GND_29_1") (pintype "power_in"))
      (node (ref "U2") (pin "29_2") (pinfunction "GND_29_2") (pintype "power_in"))
      (node (ref "U2") (pin "29_3") (pinfunction "GND_29_3") (pintype "power_in"))
      (node (ref "U2") (pin "29_4") (pinfunction "GND_29_4") (pintype "power_in"))
      (node (ref "U2") (pin "29_5") (pinfunction "GND_29_5") (pintype "power_in"))
      (node (ref "U2") (pin "29_6") (pinfunction "GND_29_6") (pintype "power_in"))
      (node (ref "U2") (pin "29_7") (pinfunction "GND_29_7") (pintype "power_in"))
      (node (ref "U2") (pin "29_8") (pinfunction "GND_29_8") (pintype "power_in"))
      (node (ref "U2") (pin "29_9") (pinfunction "GND_29_9") (pintype "power_in"))
      (node (ref "U3") (pin "13") (pinfunction "GND_13") (pintype "power_in"))
      (node (ref "U4") (pin "1") (pinfunction "CTG_1") (pintype "power_in"))
      (node (ref "U4") (pin "4") (pinfunction "GND_4") (pintype "power_in"))
      (node (ref "U4") (pin "6") (pinfunction "QSTRT_6") (pintype "input"))
      (node (ref "U4") (pin "9") (pinfunction "EP_9") (pintype "power_in"))
    )
    (net (code "14") (name "GPIO8") (class "Default")
      (node (ref "R2") (pin "1") (pinfunction "1_1") (pintype "passive"))
      (node (ref "U2") (pin "10") (pinfunction "IO8_10") (pintype "bidirectional"))
    )
    (net (code "15") (name "I2C_PW") (class "Default")
      (node (ref "C1") (pin "1") (pinfunction "1_1") (pintype "passive"))
      (node (ref "C2") (pin "1") (pinfunction "1_1") (pintype "passive"))
      (node (ref "R1_PINH") (pin "2") (pinfunction "2_2") (pintype "passive"))
      (node (ref "R2_PINH") (pin "2") (pinfunction "2_2") (pintype "passive"))
      (node (ref "SENSOR2") (pin "2") (pinfunction "CSB_2") (pintype "input"))
      (node (ref "SENSOR2") (pin "6") (pinfunction "VDDIO_6") (pintype "power_in"))
      (node (ref "SENSOR2") (pin "8") (pinfunction "VDD_8") (pintype "power_in"))
      (node (ref "U2") (pin "17") (pinfunction "IO19_17") (pintype "bidirectional"))
    )
    (net (code "16") (name "INT_RTC") (class "Default")
      (node (ref "R1_PINH1") (pin "2") (pinfunction "2_2") (pintype "passive"))
      (node (ref "TP32") (pin "TP") (pinfunction "TP_TP") (pintype "input"))
      (node (ref "U2") (pin "8") (pinfunction "IO0_8") (pintype "bidirectional"))
      (node (ref "U3") (pin "3") (pinfunction "SQW/~{INT}_3") (pintype "output"))
    )
    (net (code "17") (name "IO{slash}BOOT") (class "Default")
      (node (ref "BOOT_BUTTON") (pin "4") (pinfunction "4_4") (pintype "passive"))
      (node (ref "C6") (pin "1") (pinfunction "1_1") (pintype "passive"))
      (node (ref "R_BOOT1") (pin "1") (pinfunction "1_1") (pintype "passive"))
      (node (ref "U2") (pin "15") (pinfunction "IO9_15") (pintype "bidirectional"))
    )
    (net (code "18") (name "IO{slash}CHANGE") (class "Default")
      (node (ref "C10") (pin "1") (pinfunction "1_1") (pintype "passive"))
      (node (ref "CHANGE_BUTTON") (pin "4") (pinfunction "4_4") (pintype "passive"))
      (node (ref "R_CHANGE1") (pin "1") (pinfunction "1_1") (pintype "passive"))
      (node (ref "U2") (pin "23") (pinfunction "IO15_23") (pintype "bidirectional"))
    )
    (net (code "19") (name "MISO") (class "Default")
      (node (ref "D13") (pin "2") (pinfunction "2_2") (pintype "passive"))
      (node (ref "J4") (pin "P7") (pinfunction "DAT0_P7") (pintype "bidirectional"))
      (node (ref "R15") (pin "1") (pinfunction "1_1") (pintype "passive"))
      (node (ref "TP23") (pin "TP") (pinfunction "TP_TP") (pintype "input"))
      (node (ref "U1") (pin "2") (pinfunction "DO(IO1)_2") (pintype "bidirectional"))
      (node (ref "U2") (pin "27") (pinfunction "IO2_27") (pintype "bidirectional"))
    )
    (net (code "20") (name "MOSI") (class "Default")
      (node (ref "D14") (pin "2") (pinfunction "2_2") (pintype "passive"))
      (node (ref "FH34SRJ-24S-0.5SH_99_1") (pin "14") (pinfunction "14_14") (pintype "bidirectional"))
      (node (ref "J4") (pin "P3") (pinfunction "CMD_P3") (pintype "bidirectional"))
      (node (ref "R12") (pin "1") (pinfunction "1_1") (pintype "passive"))
      (node (ref "TP24") (pin "TP") (pinfunction "TP_TP") (pintype "input"))
      (node (ref "U1") (pin "5") (pinfunction "DI(IO0)_5") (pintype "bidirectional"))
      (node (ref "U2") (pin "7") (pinfunction "IO7_7") (pintype "bidirectional"))
    )
    (net (code "21") (name "N$12") (class "Default")
      (node (ref "EPD_C18") (pin "2") (pinfunction "2_2") (pintype "passive"))
      (node (ref "FH34SRJ-24S-0.5SH_99_1") (pin "15") (pinfunction "15_15") (pintype "bidirectional"))
      (node (ref "FH34SRJ-24S-0.5SH_99_1") (pin "16") (pinfunction "16_16") (pintype "bidirectional"))
    )
    (net (code "22") (name "Net-(CHG_LED-PadC)") (class "Default")
      (node (ref "CHG_LED") (pin "C") (pinfunction "C_C") (pintype "passive"))
      (node (ref "R1_BAT1") (pin "1") (pinfunction "1_1") (pintype "passive"))
    )
    (net (code "23") (name "Net-(D2-CATHODE)") (class "Default")
      (node (ref "C1_BAT1") (pin "1") (pinfunction "1_1") (pintype "passive"))
      (node (ref "D2") (pin "1") (pinfunction "CATHODE_1") (pintype "bidirectional"))
      (node (ref "IC4") (pin "1") (pinfunction "VIN_1") (pintype "bidirectional"))
      (node (ref "IC4") (pin "3") (pinfunction "CE_3") (pintype "bidirectional"))
    )
    (net (code "24") (name "Net-(D3-A)") (class "Default")
      (node (ref "C4") (pin "1") (pinfunction "1_1") (pintype "passive"))
      (node (ref "D3") (pin "2") (pinfunction "A_2") (pintype "bidirectional"))
      (node (ref "D4") (pin "1") (pinfunction "K_1") (pintype "bidirectional"))
    )
    (net (code "25") (name "Net-(D7-CATHODE)") (class "Default")
      (node (ref "D7") (pin "1") (pinfunction "CATHODE_1") (pintype "bidirectional"))
      (node (ref "R_CAPACITOR") (pin "2") (pinfunction "2_2") (pintype "passive"))
    )
    (net (code "26") (name "Net-(EPD_C3-Pad2)") (class "Default")
      (node (ref "EPD_C3") (pin "2") (pinfunction "2_2") (pintype "passive"))
      (node (ref "FH34SRJ-24S-0.5SH_99_1") (pin "24") (pinfunction "24_24") (pintype "bidirectional"))
    )
    (net (code "27") (name "Net-(EPD_C13-Pad2)") (class "Default")
      (node (ref "EPD_C13") (pin "2") (pinfunction "2_2") (pintype "passive"))
      (node (ref "FH34SRJ-24S-0.5SH_99_1") (pin "22") (pinfunction "22_22") (pintype "bidirectional"))
    )
    (net (code "28") (name "Net-(EPD_C15-Pad2)") (class "Default")
      (node (ref "EPD_C15") (pin "2") (pinfunction "2_2") (pintype "passive"))
      (node (ref "FH34SRJ-24S-0.5SH_99_1") (pin "20") (pinfunction "20_20") (pintype "bidirectional"))
    )
    (net (code "29") (name "Net-(EPD_C16-Pad2)") (class "Default")
      (node (ref "EPD_C16") (pin "2") (pinfunction "2_2") (pintype "passive"))
      (node (ref "FH34SRJ-24S-0.5SH_99_1") (pin "19") (pinfunction "19_19") (pintype "bidirectional"))
    )
    (net (code "30") (name "Net-(EPD_C17-Pad2)") (class "Default")
      (node (ref "EPD_C17") (pin "2") (pinfunction "2_2") (pintype "passive"))
      (node (ref "FH34SRJ-24S-0.5SH_99_1") (pin "18") (pinfunction "18_18") (pintype "bidirectional"))
    )
    (net (code "31") (name "Net-(EPD_C19-Pad2)") (class "Default")
      (node (ref "EPD_C19") (pin "2") (pinfunction "2_2") (pintype "passive"))
      (node (ref "FH34SRJ-24S-0.5SH_99_1") (pin "5") (pinfunction "5_5") (pintype "bidirectional"))
    )
    (net (code "32") (name "Net-(EPD_C20-Pad2)") (class "Default")
      (node (ref "EPD_C20") (pin "2") (pinfunction "2_2") (pintype "passive"))
      (node (ref "FH34SRJ-24S-0.5SH_99_1") (pin "4") (pinfunction "4_4") (pintype "bidirectional"))
    )
    (net (code "33") (name "Net-(IC2-CT)") (class "Default")
      (node (ref "C_DELAY1") (pin "2") (pinfunction "2_2") (pintype "passive"))
      (node (ref "IC2") (pin "5") (pinfunction "CT_5") (pintype "bidirectional"))
    )
    (net (code "34") (name "Net-(J2-PadA5)") (class "Default")
      (node (ref "J2") (pin "A5") (pinfunction "A5_A5") (pintype "bidirectional"))
      (node (ref "R2_USB1") (pin "2") (pinfunction "2_2") (pintype "passive"))
    )
    (net (code "35") (name "Net-(J2-PadB5)") (class "Default")
      (node (ref "J2") (pin "B5") (pinfunction "B5_B5") (pintype "bidirectional"))
      (node (ref "R2_USB") (pin "1") (pinfunction "1_1") (pintype "passive"))
    )
    (net (code "36") (name "Net-(MCP1-PROG)") (class "Default")
      (node (ref "MCP1") (pin "5") (pinfunction "PROG_5") (pintype "input"))
      (node (ref "R2_BAT1") (pin "2") (pinfunction "2_2") (pintype "passive"))
    )
    (net (code "37") (name "Net-(MCP1-STAT)") (class "Default")
      (node (ref "MCP1") (pin "1") (pinfunction "STAT_1") (pintype "output"))
      (node (ref "R1_BAT1") (pin "2") (pinfunction "2_2") (pintype "passive"))
    )
    (net (code "38") (name "PREVGH") (class "Default")
      (node (ref "D5") (pin "1") (pinfunction "K_1") (pintype "bidirectional"))
      (node (ref "EPD_C14") (pin "2") (pinfunction "2_2") (pintype "passive"))
      (node (ref "FH34SRJ-24S-0.5SH_99_1") (pin "21") (pinfunction "21_21") (pintype "bidirectional"))
    )
    (net (code "39") (name "PREVGL") (class "Default")
      (node (ref "D4") (pin "2") (pinfunction "A_2") (pintype "bidirectional"))
      (node (ref "EPD_C4") (pin "2") (pinfunction "2_2") (pintype "passive"))
      (node (ref "FH34SRJ-24S-0.5SH_99_1") (pin "23") (pinfunction "23_23") (pintype "bidirectional"))
    )
    (net (code "40") (name "RESE") (class "Default")
      (node (ref "FH34SRJ-24S-0.5SH_99_1") (pin "3") (pinfunction "3_3") (pintype "bidirectional"))
      (node (ref "Q3") (pin "2") (pinfunction "S_2") (pintype "bidirectional"))
      (node (ref "R11") (pin "2") (pinfunction "2_2") (pintype "passive"))
    )
    (net (code "41") (name "RESE'") (class "Default")
      (node (ref "R11") (pin "1") (pinfunction "1_1") (pintype "passive"))
      (node (ref "R3") (pin "2") (pinfunction "2_2") (pintype "passive"))
      (node (ref "SJ1") (pin "2") (pinfunction "2_2") (pintype "passive"))
    )
    (net (code "42") (name "RESET") (class "Default")
      (node (ref "C5") (pin "1") (pinfunction "1_1") (pintype "passive"))
      (node (ref "IC2") (pin "1") (pinfunction "VOUT_1") (pintype "bidirectional"))
      (node (ref "RESET_BUTTON") (pin "3") (pinfunction "3_3") (pintype "passive"))
      (node (ref "RESET_BUTTON") (pin "4") (pinfunction "4_4") (pintype "passive"))
      (node (ref "R_RESET1") (pin "1") (pinfunction "1_1") (pintype "passive"))
      (node (ref "U2") (pin "3") (pinfunction "EN_3") (pintype "input"))
    )
    (net (code "43") (name "RTC_RST") (class "Default")
      (node (ref "U2") (pin "16") (pinfunction "IO18_16") (pintype "bidirectional"))
      (node (ref "U3") (pin "4") (pinfunction "~{RST}_4") (pintype "input"))
    )
    (net (code "44") (name "RX") (class "Default")
      (node (ref "TP19") (pin "TP") (pinfunction "TP_TP") (pintype "input"))
      (node (ref "U2") (pin "24") (pinfunction "RXD0/GPIO17_24") (pintype "bidirectional"))
    )
    (net (code "45") (name "SCK") (class "Default")
      (node (ref "D15") (pin "2") (pinfunction "2_2") (pintype "passive"))
      (node (ref "FH34SRJ-24S-0.5SH_99_1") (pin "13") (pinfunction "13_13") (pintype "bidirectional"))
      (node (ref "J4") (pin "P5") (pinfunction "CLK_P5") (pintype "bidirectional"))
      (node (ref "R13") (pin "1") (pinfunction "1_1") (pintype "passive"))
      (node (ref "TP25") (pin "TP") (pinfunction "TP_TP") (pintype "input"))
      (node (ref "U1") (pin "6") (pinfunction "CLK_6") (pintype "input"))
      (node (ref "U2") (pin "6") (pinfunction "IO6_6") (pintype "bidirectional"))
    )
    (net (code "46") (name "SCL") (class "Default")
      (node (ref "J1") (pin "4") (pinfunction "4_4") (pintype "passive"))
      (node (ref "R2_PINH") (pin "1") (pinfunction "1_1") (pintype "passive"))
      (node (ref "SENSOR2") (pin "4") (pinfunction "SCK_4") (pintype "input"))
      (node (ref "U2") (pin "20") (pinfunction "IO22_20") (pintype "bidirectional"))
      (node (ref "U3") (pin "16") (pinfunction "SCL_16") (pintype "input"))
      (node (ref "U4") (pin "7") (pinfunction "SCL_7") (pintype "input"))
    )
    (net (code "47") (name "SDA") (class "Default")
      (node (ref "J1") (pin "3") (pinfunction "3_3") (pintype "passive"))
      (node (ref "R1_PINH") (pin "1") (pinfunction "1_1") (pintype "passive"))
      (node (ref "SENSOR2") (pin "3") (pinfunction "SDI_3") (pintype "bidirectional"))
      (node (ref "U2") (pin "19") (pinfunction "IO21_19") (pintype "bidirectional"))
      (node (ref "U3") (pin "15") (pinfunction "SDA_15") (pintype "bidirectional"))
      (node (ref "U4") (pin "8") (pinfunction "SDA_8") (pintype "bidirectional"))
    )
    (net (code "48") (name "SRC") (class "Default")
      (node (ref "C4") (pin "2") (pinfunction "2_2") (pintype "passive"))
      (node (ref "D5") (pin "2") (pinfunction "A_2") (pintype "bidirectional"))
      (node (ref "L1") (pin "1") (pinfunction "1_1") (pintype "passive"))
      (node (ref "Q3") (pin "3") (pinfunction "D_3") (pintype "bidirectional"))
    )
    (net (code "49") (name "SS_SD") (class "Default")
      (node (ref "D18") (pin "2") (pinfunction "2_2") (pintype "passive"))
      (node (ref "J4") (pin "P2") (pinfunction "CD/DAT3_P2") (pintype "bidirectional"))
      (node (ref "R17") (pin "1") (pinfunction "1_1") (pintype "passive"))
      (node (ref "U2") (pin "4") (pinfunction "IO4_4") (pintype "bidirectional"))
    )
    (net (code "50") (name "TX") (class "Default")
      (node (ref "TP18") (pin "TP") (pinfunction "TP_TP") (pintype "input"))
      (node (ref "U2") (pin "25") (pinfunction "TXD0/GPIO16_25") (pintype "bidirectional"))
    )
    (net (code "51") (name "USB_D+") (class "Default")
      (node (ref "D1") (pin "3") (pinfunction "I/O2_1_3") (pintype "bidirectional"))
      (node (ref "U2") (pin "14") (pinfunction "IO13_14") (pintype "bidirectional"))
    )
    (net (code "52") (name "USB_D-") (class "Default")
      (node (ref "D1") (pin "1") (pinfunction "I/O1_1_1") (pintype "bidirectional"))
      (node (ref "U2") (pin "13") (pinfunction "IO12_13") (pintype "bidirectional"))
    )
    (net (code "53") (name "VBAT") (class "Default")
      (node (ref "C2_BAT1") (pin "1") (pinfunction "1_1") (pintype "passive"))
      (node (ref "MCP1") (pin "3") (pinfunction "VBAT_3") (pintype "power_in"))
      (node (ref "Q1") (pin "3") (pinfunction "D_3") (pintype "bidirectional"))
      (node (ref "TP20") (pin "TP") (pinfunction "TP_TP") (pintype "input"))
      (node (ref "U4") (pin "2") (pinfunction "CELL_2") (pintype "power_in"))
      (node (ref "U4") (pin "3") (pinfunction "VDD_3") (pintype "power_in"))
    )
    (net (code "54") (name "VBUS") (class "Default")
      (node (ref "C1_BAT3") (pin "1") (pinfunction "1_1") (pintype "passive"))
      (node (ref "C4_USB") (pin "1") (pinfunction "1_1") (pintype "passive"))
      (node (ref "C5_USB") (pin "1") (pinfunction "1_1") (pintype "passive"))
      (node (ref "CHG_LED") (pin "A") (pinfunction "A_A") (pintype "passive"))
      (node (ref "D1") (pin "5") (pinfunction "VBUS_5") (pintype "bidirectional"))
      (node (ref "D2") (pin "2") (pinfunction "ANODE_2") (pintype "bidirectional"))
      (node (ref "MCP1") (pin "4") (pinfunction "VIN_4") (pintype "power_in"))
      (node (ref "PFMF.050.1") (pin "2") (pinfunction "2_2") (pintype "passive"))
      (node (ref "Q1") (pin "1") (pinfunction "G_1") (pintype "bidirectional"))
      (node (ref "R1_PWRUSB") (pin "2") (pinfunction "2_2") (pintype "passive"))
      (node (ref "TP31") (pin "TP") (pinfunction "TP_TP") (pintype "input"))
    )
    (net (code "55") (name "VRTC") (class "Default")
      (node (ref "C10_SUPERCAP") (pin "1") (pinfunction "1_1") (pintype "passive"))
      (node (ref "C8") (pin "1") (pinfunction "1_1") (pintype "passive"))
      (node (ref "R_CAPACITOR") (pin "1") (pinfunction "1_1") (pintype "passive"))
      (node (ref "U3") (pin "14") (pinfunction "VBAT_14") (pintype "power_in"))
    )
    (net (code "56") (name "VUSB") (class "Default")
      (node (ref "J2") (pin "A4") (pinfunction "A4_A4") (pintype "bidirectional"))
      (node (ref "J2") (pin "A9") (pinfunction "A9_A9") (pintype "bidirectional"))
      (node (ref "J2") (pin "B4") (pinfunction "B4_B4") (pintype "bidirectional"))
      (node (ref "J2") (pin "B9") (pinfunction "B9_B9") (pintype "bidirectional"))
      (node (ref "PFMF.050.1") (pin "1") (pinfunction "1_1") (pintype "passive"))
    )
    (net (code "57") (name "unconnected-(BOOT_BUTTON-Pad1)") (class "Default")
      (node (ref "BOOT_BUTTON") (pin "1") (pinfunction "1_1") (pintype "passive"))
    )
    (net (code "58") (name "unconnected-(BOOT_BUTTON-Pad3)") (class "Default")
      (node (ref "BOOT_BUTTON") (pin "3") (pinfunction "3_3") (pintype "passive"))
    )
    (net (code "59") (name "unconnected-(CHANGE_BUTTON-Pad1)") (class "Default")
      (node (ref "CHANGE_BUTTON") (pin "1") (pinfunction "1_1") (pintype "passive"))
    )
    (net (code "60") (name "unconnected-(CHANGE_BUTTON-Pad3)") (class "Default")
      (node (ref "CHANGE_BUTTON") (pin "3") (pinfunction "3_3") (pintype "passive"))
    )
    (net (code "61") (name "unconnected-(FH34SRJ-24S-0.5SH_99_1-Pad1)") (class "Default")
      (node (ref "FH34SRJ-24S-0.5SH_99_1") (pin "1") (pinfunction "1_1") (pintype "bidirectional"))
    )
    (net (code "62") (name "unconnected-(FH34SRJ-24S-0.5SH_99_1-Pad6)") (class "Default")
      (node (ref "FH34SRJ-24S-0.5SH_99_1") (pin "6") (pinfunction "6_6") (pintype "bidirectional"))
    )
    (net (code "63") (name "unconnected-(FH34SRJ-24S-0.5SH_99_1-Pad7)") (class "Default")
      (node (ref "FH34SRJ-24S-0.5SH_99_1") (pin "7") (pinfunction "7_7") (pintype "bidirectional"))
    )
    (net (code "64") (name "unconnected-(IC2-NC-Pad4)") (class "Default")
      (node (ref "IC2") (pin "4") (pinfunction "NC_4") (pintype "no_connect"))
    )
    (net (code "65") (name "unconnected-(IC4-NC-Pad4)") (class "Default")
      (node (ref "IC4") (pin "4") (pinfunction "NC_4") (pintype "no_connect"))
    )
    (net (code "66") (name "unconnected-(J2-PadA6)") (class "Default")
      (node (ref "J2") (pin "A6") (pinfunction "A6_A6") (pintype "bidirectional"))
    )
    (net (code "67") (name "unconnected-(J2-PadB8)") (class "Default")
      (node (ref "J2") (pin "B8") (pinfunction "B8_B8") (pintype "bidirectional"))
    )
    (net (code "68") (name "unconnected-(J4-DAT1-PadP8)") (class "Default")
      (node (ref "J4") (pin "P8") (pinfunction "DAT1_P8") (pintype "bidirectional"))
    )
    (net (code "69") (name "unconnected-(J4-DAT2-PadP1)") (class "Default")
      (node (ref "J4") (pin "P1") (pinfunction "DAT2_P1") (pintype "bidirectional"))
    )
    (net (code "70") (name "unconnected-(J4-DETECTION_1-PadS1)") (class "Default")
      (node (ref "J4") (pin "S1") (pinfunction "DETECTION_1_S1") (pintype "bidirectional"))
    )
    (net (code "71") (name "unconnected-(J4-DETECTION_2-PadS2)") (class "Default")
      (node (ref "J4") (pin "S2") (pinfunction "DETECTION_2_S2") (pintype "bidirectional"))
    )
    (net (code "72") (name "unconnected-(Q1-S-Pad2)") (class "Default")
      (node (ref "Q1") (pin "2") (pinfunction "S_2") (pintype "bidirectional"))
    )
    (net (code "73") (name "unconnected-(U2-NC-Pad22)") (class "Default")
      (node (ref "U2") (pin "22") (pinfunction "NC_22") (pintype "no_connect"))
    )
    (net (code "74") (name "unconnected-(U4-~{ALERT}-Pad5)") (class "Default")
      (node (ref "U4") (pin "5") (pinfunction "~{ALERT}_5") (pintype "output"))
    )
  )
)
